# LAUNCHXL-F28379D_9.net
KiCad netlist of a schematic drawn in Altium Designer
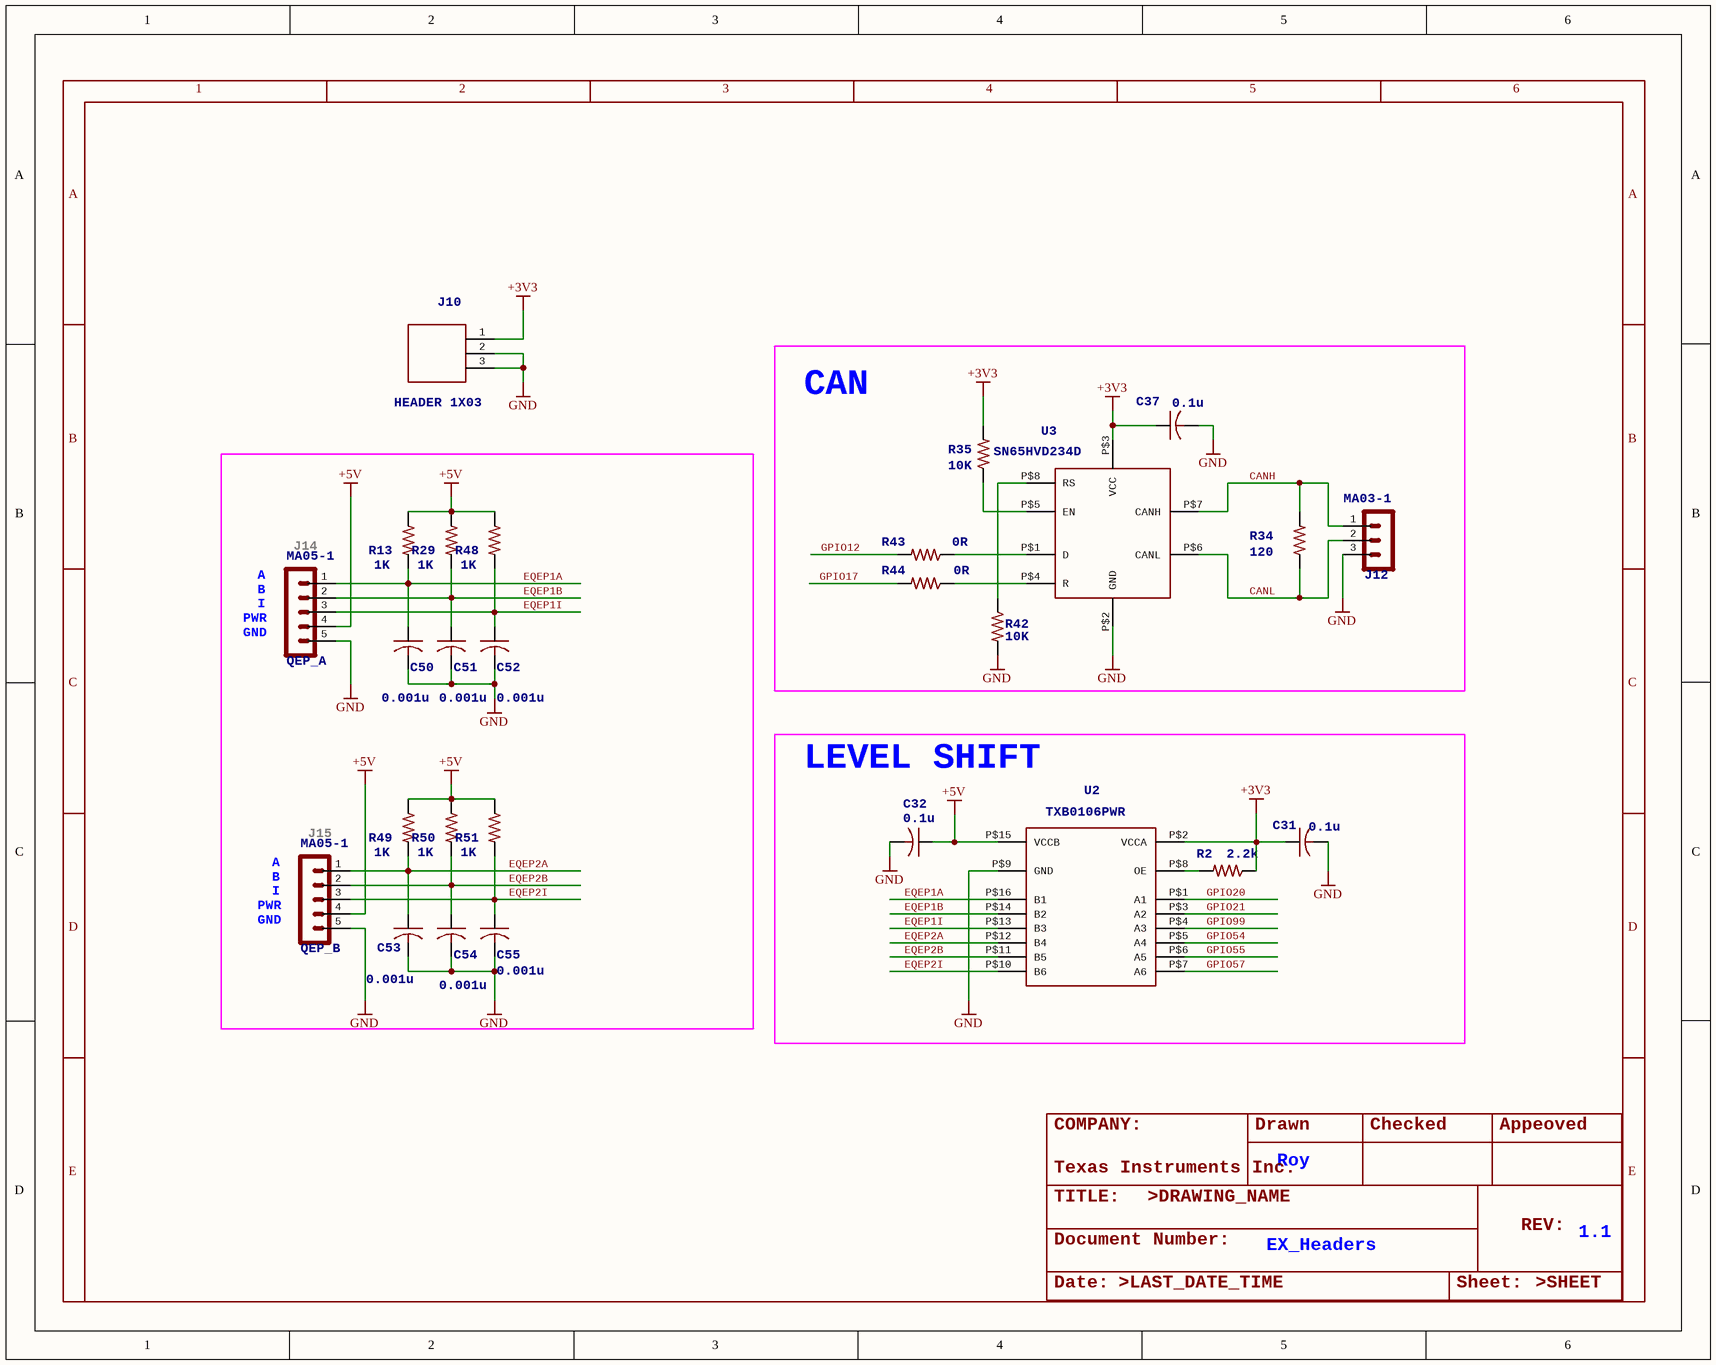
[diagram p0: LAUNCHXL-F28379D_9.SchDoc]

(export (version "E")
  (design (tool "Eeschema 10.0.6"))
  (components
    (comp (ref "C31")
      (value "0.1u")
      (footprint "C0402")
      (description "<B>CAPACITOR</B>, American symbol")
      (libsource (lib "rcl") (part "C-USC0402"))
    )
    (comp (ref "C32")
      (value "0.1u")
      (footprint "C0402")
      (description "<B>CAPACITOR</B>, American symbol")
      (libsource (lib "rcl") (part "C-USC0402"))
    )
    (comp (ref "C37")
      (value "0.1u")
      (footprint "C0402")
      (description "<B>CAPACITOR</B>, American symbol")
      (libsource (lib "rcl") (part "C-USC0402"))
    )
    (comp (ref "C50")
      (value "0.001u")
      (footprint "C0402")
      (description "<B>CAPACITOR</B>, American symbol")
      (libsource (lib "rcl") (part "C-USC0402"))
    )
    (comp (ref "C51")
      (value "0.001u")
      (footprint "C0402")
      (description "<B>CAPACITOR</B>, American symbol")
      (libsource (lib "rcl") (part "C-USC0402"))
    )
    (comp (ref "C52")
      (value "0.001u")
      (footprint "C0402")
      (description "<B>CAPACITOR</B>, American symbol")
      (libsource (lib "rcl") (part "C-USC0402"))
    )
    (comp (ref "C53")
      (value "0.001u")
      (footprint "C0402")
      (description "<B>CAPACITOR</B>, American symbol")
      (libsource (lib "rcl") (part "C-USC0402"))
    )
    (comp (ref "C54")
      (value "0.001u")
      (footprint "C0402")
      (description "<B>CAPACITOR</B>, American symbol")
      (libsource (lib "rcl") (part "C-USC0402"))
    )
    (comp (ref "C55")
      (value "0.001u")
      (footprint "C0402")
      (description "<B>CAPACITOR</B>, American symbol")
      (libsource (lib "rcl") (part "C-USC0402"))
    )
    (comp (ref "J10")
      (value "HEADER 1X03")
      (footprint "3PIN_PWR_3V3")
      (libsource (lib "LaunchPad_Template_Library") (part "BP_HEADERS_PWR_3V3-TH"))
    )
    (comp (ref "J12")
      (value "MA03-1")
      (footprint "MA03-1")
      (description "<b>PIN HEADER</b>")
      (libsource (lib "con-lstb") (part "MA03-1"))
    )
    (comp (ref "QEP_A")
      (value "MA05-1")
      (footprint "MA05-1")
      (description "<b>PIN HEADER</b>")
      (libsource (lib "con-lstb") (part "MA05-1"))
    )
    (comp (ref "QEP_B")
      (value "MA05-1")
      (footprint "MA05-1")
      (description "<b>PIN HEADER</b>")
      (libsource (lib "con-lstb") (part "MA05-1"))
    )
    (comp (ref "R2")
      (value "2.2k")
      (footprint "R0402")
      (description "<B>RESISTOR</B>, American symbol")
      (libsource (lib "rcl") (part "R-US_R0402"))
    )
    (comp (ref "R13")
      (value "1K")
      (footprint "R0402")
      (description "<B>RESISTOR</B>, American symbol")
      (libsource (lib "rcl") (part "R-US_R0402"))
    )
    (comp (ref "R29")
      (value "1K")
      (footprint "R0402")
      (description "<B>RESISTOR</B>, American symbol")
      (libsource (lib "rcl") (part "R-US_R0402"))
    )
    (comp (ref "R34")
      (value "120")
      (footprint "R0402")
      (description "<B>RESISTOR</B>, American symbol")
      (libsource (lib "rcl") (part "R-US_R0402"))
    )
    (comp (ref "R35")
      (value "10K")
      (footprint "R0402")
      (description "<B>RESISTOR</B>, American symbol")
      (libsource (lib "rcl") (part "R-US_R0402"))
    )
    (comp (ref "R42")
      (value "10K")
      (footprint "R0402")
      (description "<B>RESISTOR</B>, American symbol")
      (libsource (lib "rcl") (part "R-US_R0402"))
    )
    (comp (ref "R43")
      (value "0R")
      (footprint "R0402")
      (description "<B>RESISTOR</B>, American symbol")
      (libsource (lib "rcl") (part "R-US_R0402"))
    )
    (comp (ref "R44")
      (value "0R")
      (footprint "R0402")
      (description "<B>RESISTOR</B>, American symbol")
      (libsource (lib "rcl") (part "R-US_R0402"))
    )
    (comp (ref "R48")
      (value "1K")
      (footprint "R0402")
      (description "<B>RESISTOR</B>, American symbol")
      (libsource (lib "rcl") (part "R-US_R0402"))
    )
    (comp (ref "R49")
      (value "1K")
      (footprint "R0402")
      (description "<B>RESISTOR</B>, American symbol")
      (libsource (lib "rcl") (part "R-US_R0402"))
    )
    (comp (ref "R50")
      (value "1K")
      (footprint "R0402")
      (description "<B>RESISTOR</B>, American symbol")
      (libsource (lib "rcl") (part "R-US_R0402"))
    )
    (comp (ref "R51")
      (value "1K")
      (footprint "R0402")
      (description "<B>RESISTOR</B>, American symbol")
      (libsource (lib "rcl") (part "R-US_R0402"))
    )
    (comp (ref "U2")
      (value "TXB0106PWR")
      (footprint "TSSOP16-PW")
      (libsource (lib "LAUNCHXL-F28027") (part "TXB0106PWR"))
    )
    (comp (ref "U3")
      (value "SN65HVD234D")
      (footprint "SOIC8-PDSO")
      (libsource (lib "LAUNCHXL-F28027") (part "SN65HVD234D"))
    )
  )
  (nets
    (net (code "1") (name "+3V3") (class "Default")
      (node (ref "C31") (pin "1") (pinfunction "1_1") (pintype "passive"))
      (node (ref "C37") (pin "1") (pinfunction "1_1") (pintype "passive"))
      (node (ref "J10") (pin "1") (pinfunction "1_1") (pintype "passive"))
      (node (ref "R2") (pin "1") (pinfunction "1_1") (pintype "passive"))
      (node (ref "R35") (pin "2") (pinfunction "2_2") (pintype "passive"))
      (node (ref "U2") (pin "P$2") (pinfunction "VCCA_P$2") (pintype "passive"))
      (node (ref "U3") (pin "P$3") (pinfunction "VCC_P$3") (pintype "passive"))
    )
    (net (code "2") (name "+5V") (class "Default")
      (node (ref "C32") (pin "1") (pinfunction "1_1") (pintype "passive"))
      (node (ref "QEP_A") (pin "4") (pinfunction "4_4") (pintype "passive"))
      (node (ref "QEP_B") (pin "4") (pinfunction "4_4") (pintype "passive"))
      (node (ref "R13") (pin "1") (pinfunction "1_1") (pintype "passive"))
      (node (ref "R29") (pin "1") (pinfunction "1_1") (pintype "passive"))
      (node (ref "R48") (pin "1") (pinfunction "1_1") (pintype "passive"))
      (node (ref "R49") (pin "1") (pinfunction "1_1") (pintype "passive"))
      (node (ref "R50") (pin "1") (pinfunction "1_1") (pintype "passive"))
      (node (ref "R51") (pin "1") (pinfunction "1_1") (pintype "passive"))
      (node (ref "U2") (pin "P$15") (pinfunction "VCCB_P$15") (pintype "passive"))
    )
    (net (code "3") (name "/CANH") (class "Default")
      (node (ref "J12") (pin "1") (pinfunction "1_1") (pintype "passive"))
      (node (ref "R34") (pin "2") (pinfunction "2_2") (pintype "passive"))
      (node (ref "U3") (pin "P$7") (pinfunction "CANH_P$7") (pintype "passive"))
    )
    (net (code "4") (name "/CANL") (class "Default")
      (node (ref "J12") (pin "2") (pinfunction "2_2") (pintype "passive"))
      (node (ref "R34") (pin "1") (pinfunction "1_1") (pintype "passive"))
      (node (ref "U3") (pin "P$6") (pinfunction "CANL_P$6") (pintype "passive"))
    )
    (net (code "5") (name "/EQEP1A") (class "Default")
      (node (ref "C50") (pin "1") (pinfunction "1_1") (pintype "passive"))
      (node (ref "QEP_A") (pin "1") (pinfunction "1_1") (pintype "passive"))
      (node (ref "R13") (pin "2") (pinfunction "2_2") (pintype "passive"))
      (node (ref "U2") (pin "P$16") (pinfunction "B1_P$16") (pintype "passive"))
    )
    (net (code "6") (name "/EQEP1B") (class "Default")
      (node (ref "C51") (pin "1") (pinfunction "1_1") (pintype "passive"))
      (node (ref "QEP_A") (pin "2") (pinfunction "2_2") (pintype "passive"))
      (node (ref "R29") (pin "2") (pinfunction "2_2") (pintype "passive"))
      (node (ref "U2") (pin "P$14") (pinfunction "B2_P$14") (pintype "passive"))
    )
    (net (code "7") (name "/EQEP1I") (class "Default")
      (node (ref "C52") (pin "1") (pinfunction "1_1") (pintype "passive"))
      (node (ref "QEP_A") (pin "3") (pinfunction "3_3") (pintype "passive"))
      (node (ref "R48") (pin "2") (pinfunction "2_2") (pintype "passive"))
      (node (ref "U2") (pin "P$13") (pinfunction "B3_P$13") (pintype "passive"))
    )
    (net (code "8") (name "/EQEP2A") (class "Default")
      (node (ref "C53") (pin "1") (pinfunction "1_1") (pintype "passive"))
      (node (ref "QEP_B") (pin "1") (pinfunction "1_1") (pintype "passive"))
      (node (ref "R49") (pin "2") (pinfunction "2_2") (pintype "passive"))
      (node (ref "U2") (pin "P$12") (pinfunction "B4_P$12") (pintype "passive"))
    )
    (net (code "9") (name "/EQEP2B") (class "Default")
      (node (ref "C54") (pin "1") (pinfunction "1_1") (pintype "passive"))
      (node (ref "QEP_B") (pin "2") (pinfunction "2_2") (pintype "passive"))
      (node (ref "R50") (pin "2") (pinfunction "2_2") (pintype "passive"))
      (node (ref "U2") (pin "P$11") (pinfunction "B5_P$11") (pintype "passive"))
    )
    (net (code "10") (name "/EQEP2I") (class "Default")
      (node (ref "C55") (pin "1") (pinfunction "1_1") (pintype "passive"))
      (node (ref "QEP_B") (pin "3") (pinfunction "3_3") (pintype "passive"))
      (node (ref "R51") (pin "2") (pinfunction "2_2") (pintype "passive"))
      (node (ref "U2") (pin "P$10") (pinfunction "B6_P$10") (pintype "passive"))
    )
    (net (code "11") (name "/GPIO12") (class "Default")
      (node (ref "R43") (pin "2") (pinfunction "2_2") (pintype "passive"))
    )
    (net (code "12") (name "/GPIO17") (class "Default")
      (node (ref "R44") (pin "2") (pinfunction "2_2") (pintype "passive"))
    )
    (net (code "13") (name "/GPIO20") (class "Default")
      (node (ref "U2") (pin "P$1") (pinfunction "A1_P$1") (pintype "passive"))
    )
    (net (code "14") (name "/GPIO21") (class "Default")
      (node (ref "U2") (pin "P$3") (pinfunction "A2_P$3") (pintype "passive"))
    )
    (net (code "15") (name "/GPIO54") (class "Default")
      (node (ref "U2") (pin "P$5") (pinfunction "A4_P$5") (pintype "passive"))
    )
    (net (code "16") (name "/GPIO55") (class "Default")
      (node (ref "U2") (pin "P$6") (pinfunction "A5_P$6") (pintype "passive"))
    )
    (net (code "17") (name "/GPIO57") (class "Default")
      (node (ref "U2") (pin "P$7") (pinfunction "A6_P$7") (pintype "passive"))
    )
    (net (code "18") (name "/GPIO99") (class "Default")
      (node (ref "U2") (pin "P$4") (pinfunction "A3_P$4") (pintype "passive"))
    )
    (net (code "19") (name "GND") (class "Default")
      (node (ref "C31") (pin "2") (pinfunction "2_2") (pintype "passive"))
      (node (ref "C32") (pin "2") (pinfunction "2_2") (pintype "passive"))
      (node (ref "C37") (pin "2") (pinfunction "2_2") (pintype "passive"))
      (node (ref "C50") (pin "2") (pinfunction "2_2") (pintype "passive"))
      (node (ref "C51") (pin "2") (pinfunction "2_2") (pintype "passive"))
      (node (ref "C52") (pin "2") (pinfunction "2_2") (pintype "passive"))
      (node (ref "C53") (pin "2") (pinfunction "2_2") (pintype "passive"))
      (node (ref "C54") (pin "2") (pinfunction "2_2") (pintype "passive"))
      (node (ref "C55") (pin "2") (pinfunction "2_2") (pintype "passive"))
      (node (ref "J10") (pin "2") (pinfunction "2_2") (pintype "passive"))
      (node (ref "J10") (pin "3") (pinfunction "3_3") (pintype "passive"))
      (node (ref "J12") (pin "3") (pinfunction "3_3") (pintype "passive"))
      (node (ref "QEP_A") (pin "5") (pinfunction "5_5") (pintype "passive"))
      (node (ref "QEP_B") (pin "5") (pinfunction "5_5") (pintype "passive"))
      (node (ref "R42") (pin "2") (pinfunction "2_2") (pintype "passive"))
      (node (ref "U2") (pin "P$9") (pinfunction "GND_P$9") (pintype "passive"))
      (node (ref "U3") (pin "P$2") (pinfunction "GND_P$2") (pintype "passive"))
    )
    (net (code "20") (name "Net-(U2-OE)") (class "Default")
      (node (ref "R2") (pin "2") (pinfunction "2_2") (pintype "passive"))
      (node (ref "U2") (pin "P$8") (pinfunction "OE_P$8") (pintype "passive"))
    )
    (net (code "21") (name "Net-(U3-D)") (class "Default")
      (node (ref "R43") (pin "1") (pinfunction "1_1") (pintype "passive"))
      (node (ref "U3") (pin "P$1") (pinfunction "D_P$1") (pintype "passive"))
    )
    (net (code "22") (name "Net-(U3-EN)") (class "Default")
      (node (ref "R35") (pin "1") (pinfunction "1_1") (pintype "passive"))
      (node (ref "U3") (pin "P$5") (pinfunction "EN_P$5") (pintype "passive"))
    )
    (net (code "23") (name "Net-(U3-R)") (class "Default")
      (node (ref "R44") (pin "1") (pinfunction "1_1") (pintype "passive"))
      (node (ref "U3") (pin "P$4") (pinfunction "R_P$4") (pintype "passive"))
    )
    (net (code "24") (name "Net-(U3-RS)") (class "Default")
      (node (ref "R42") (pin "1") (pinfunction "1_1") (pintype "passive"))
      (node (ref "U3") (pin "P$8") (pinfunction "RS_P$8") (pintype "passive"))
    )
  )
)
